# TempStanchion_v3.net
KiCad netlist of a schematic drawn in EAGLE
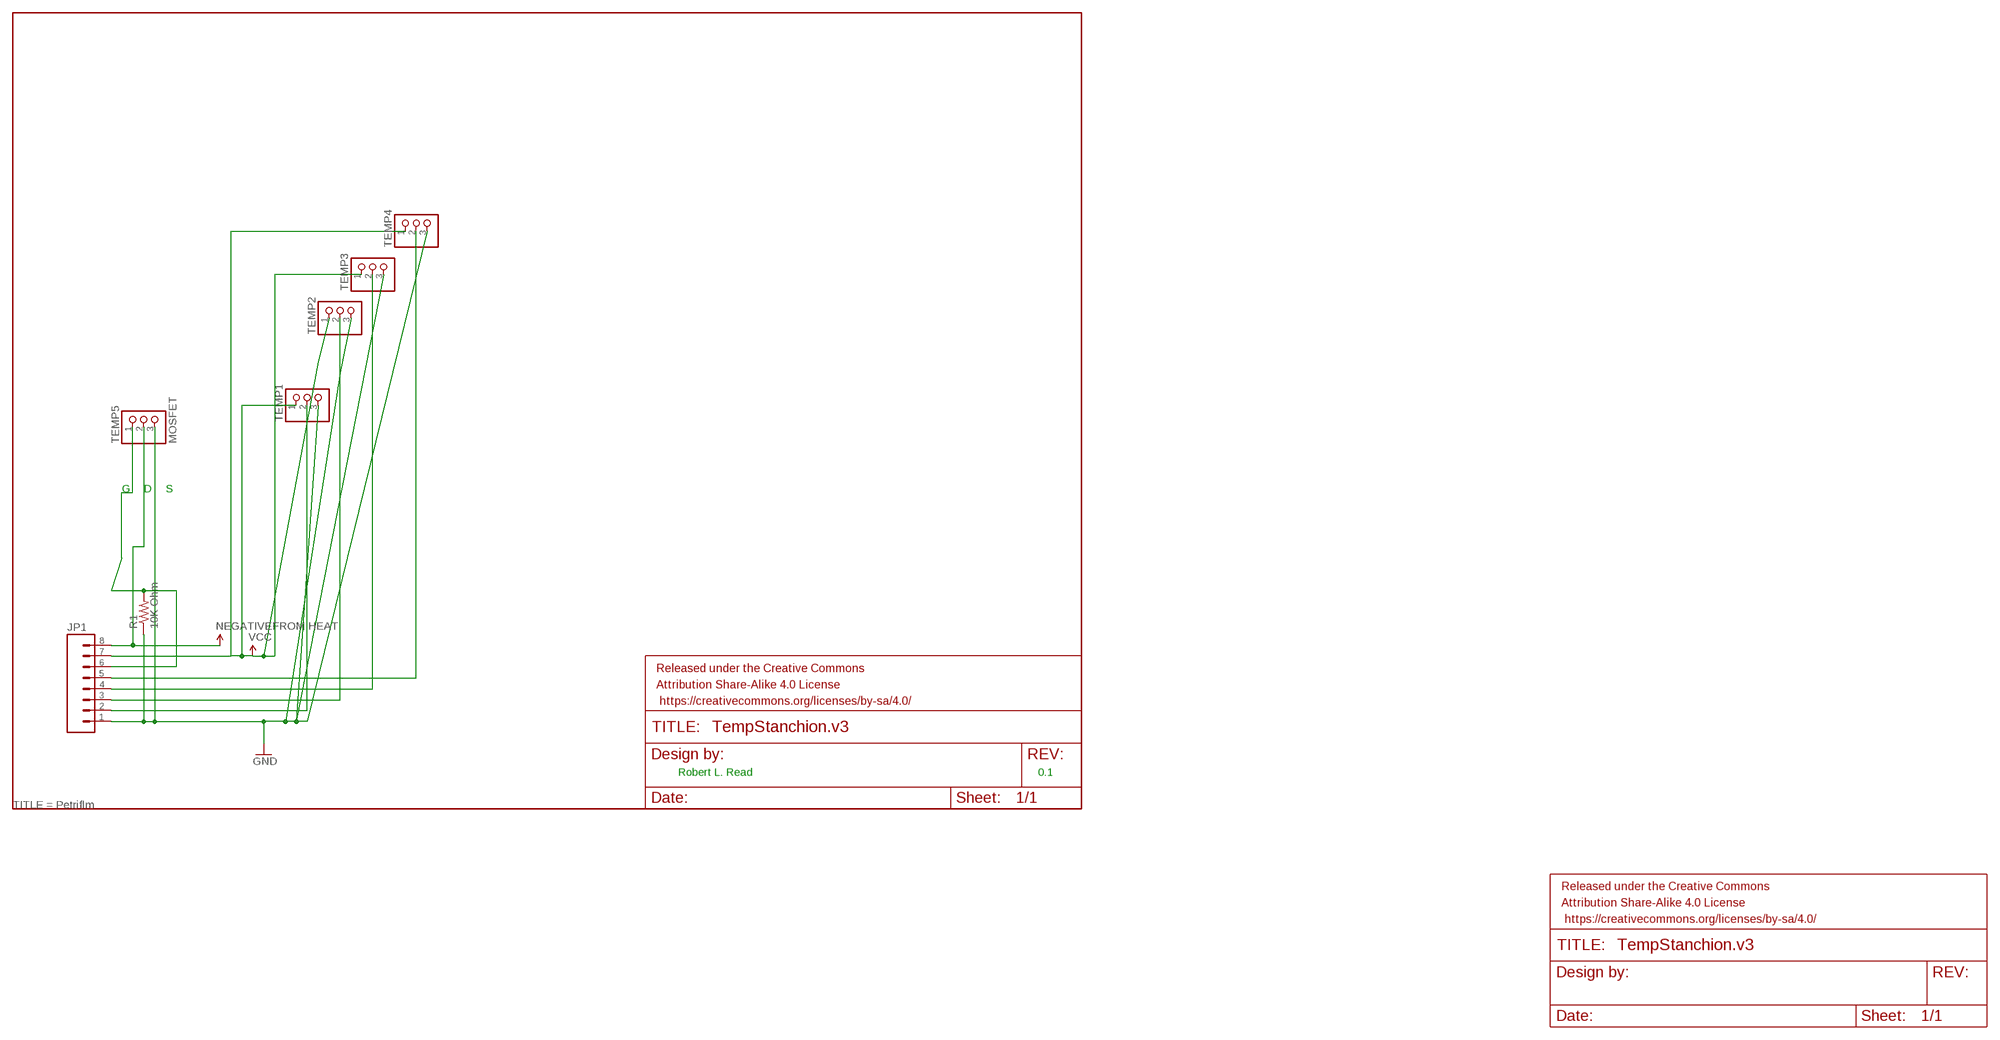
[diagram p0: schematic, sheet 1]

(export (version "E")
  (design (tool "Eeschema 10.0.6"))
  (components
    (comp (ref "FRAME1")
      (value "FRAME-LETTER")
      (footprint "eagle-import:CREATIVE_COMMONS")
      (libsource (lib "eagle-import") (part "FRAME-LETTER"))
    )
    (comp (ref "FRAME2")
      (value "FRAME-LETTER")
      (footprint "eagle-import:CREATIVE_COMMONS")
      (fields (field (name "TITLE") "Petriflm"))
      (libsource (lib "eagle-import") (part "FRAME-LETTER"))
    )
    (comp (ref "JP1")
      (value "M08")
      (footprint "eagle-import:1X08_ROUND")
      (libsource (lib "eagle-import") (part "M08"))
    )
    (comp (ref "R1")
      (value "10K Ohm")
      (footprint "eagle-import:AXIAL-0.6")
      (libsource (lib "eagle-import") (part "RESISTORPTH-1W"))
    )
    (comp (ref "TEMP1")
      (value "PINHD-1X3")
      (footprint "eagle-import:1X03")
      (libsource (lib "eagle-import") (part "PINHD-1X3"))
    )
    (comp (ref "TEMP2")
      (value "PINHD-1X3")
      (footprint "eagle-import:1X03")
      (libsource (lib "eagle-import") (part "PINHD-1X3"))
    )
    (comp (ref "TEMP3")
      (value "PINHD-1X3")
      (footprint "eagle-import:1X03")
      (libsource (lib "eagle-import") (part "PINHD-1X3"))
    )
    (comp (ref "TEMP4")
      (value "PINHD-1X3")
      (footprint "eagle-import:1X03")
      (libsource (lib "eagle-import") (part "PINHD-1X3"))
    )
    (comp (ref "TEMP5")
      (value "MOSFET")
      (footprint "eagle-import:1X03")
      (libsource (lib "eagle-import") (part "PINHD-1X3"))
    )
  )
  (nets
    (net (code "1") (name "GND") (class "Default")
      (node (ref "JP1") (pin "1") (pinfunction "1_1") (pintype "passive"))
      (node (ref "R1") (pin "P$1") (pinfunction "1_P$1") (pintype "passive"))
      (node (ref "TEMP1") (pin "3") (pinfunction "3_3") (pintype "passive"))
      (node (ref "TEMP2") (pin "3") (pinfunction "3_3") (pintype "passive"))
      (node (ref "TEMP3") (pin "3") (pinfunction "3_3") (pintype "passive"))
      (node (ref "TEMP4") (pin "3") (pinfunction "3_3") (pintype "passive"))
      (node (ref "TEMP5") (pin "3") (pinfunction "3_3") (pintype "passive"))
    )
    (net (code "2") (name "NEGATIVEFROM HEAT") (class "Default")
      (node (ref "JP1") (pin "7") (pinfunction "7_7") (pintype "passive"))
      (node (ref "JP1") (pin "8") (pinfunction "8_8") (pintype "passive"))
      (node (ref "TEMP1") (pin "1") (pinfunction "1_1") (pintype "passive"))
      (node (ref "TEMP2") (pin "1") (pinfunction "1_1") (pintype "passive"))
      (node (ref "TEMP3") (pin "1") (pinfunction "1_1") (pintype "passive"))
      (node (ref "TEMP4") (pin "1") (pinfunction "1_1") (pintype "passive"))
      (node (ref "TEMP5") (pin "2") (pinfunction "2_2") (pintype "passive"))
    )
    (net (code "3") (name "Net-(JP1-Pad2)") (class "Default")
      (node (ref "JP1") (pin "2") (pinfunction "2_2") (pintype "passive"))
      (node (ref "TEMP1") (pin "2") (pinfunction "2_2") (pintype "passive"))
    )
    (net (code "4") (name "Net-(JP1-Pad3)") (class "Default")
      (node (ref "JP1") (pin "3") (pinfunction "3_3") (pintype "passive"))
      (node (ref "TEMP2") (pin "2") (pinfunction "2_2") (pintype "passive"))
    )
    (net (code "5") (name "Net-(JP1-Pad4)") (class "Default")
      (node (ref "JP1") (pin "4") (pinfunction "4_4") (pintype "passive"))
      (node (ref "TEMP3") (pin "2") (pinfunction "2_2") (pintype "passive"))
    )
    (net (code "6") (name "Net-(JP1-Pad5)") (class "Default")
      (node (ref "JP1") (pin "5") (pinfunction "5_5") (pintype "passive"))
      (node (ref "TEMP4") (pin "2") (pinfunction "2_2") (pintype "passive"))
    )
    (net (code "7") (name "Net-(R1-2)") (class "Default")
      (node (ref "JP1") (pin "6") (pinfunction "6_6") (pintype "passive"))
      (node (ref "R1") (pin "P$2") (pinfunction "2_P$2") (pintype "passive"))
      (node (ref "TEMP5") (pin "1") (pinfunction "1_1") (pintype "passive"))
    )
  )
)
